# Waveshape_LFO_v1_Controls_SCH.net
KiCad netlist of a schematic drawn in Altium Designer
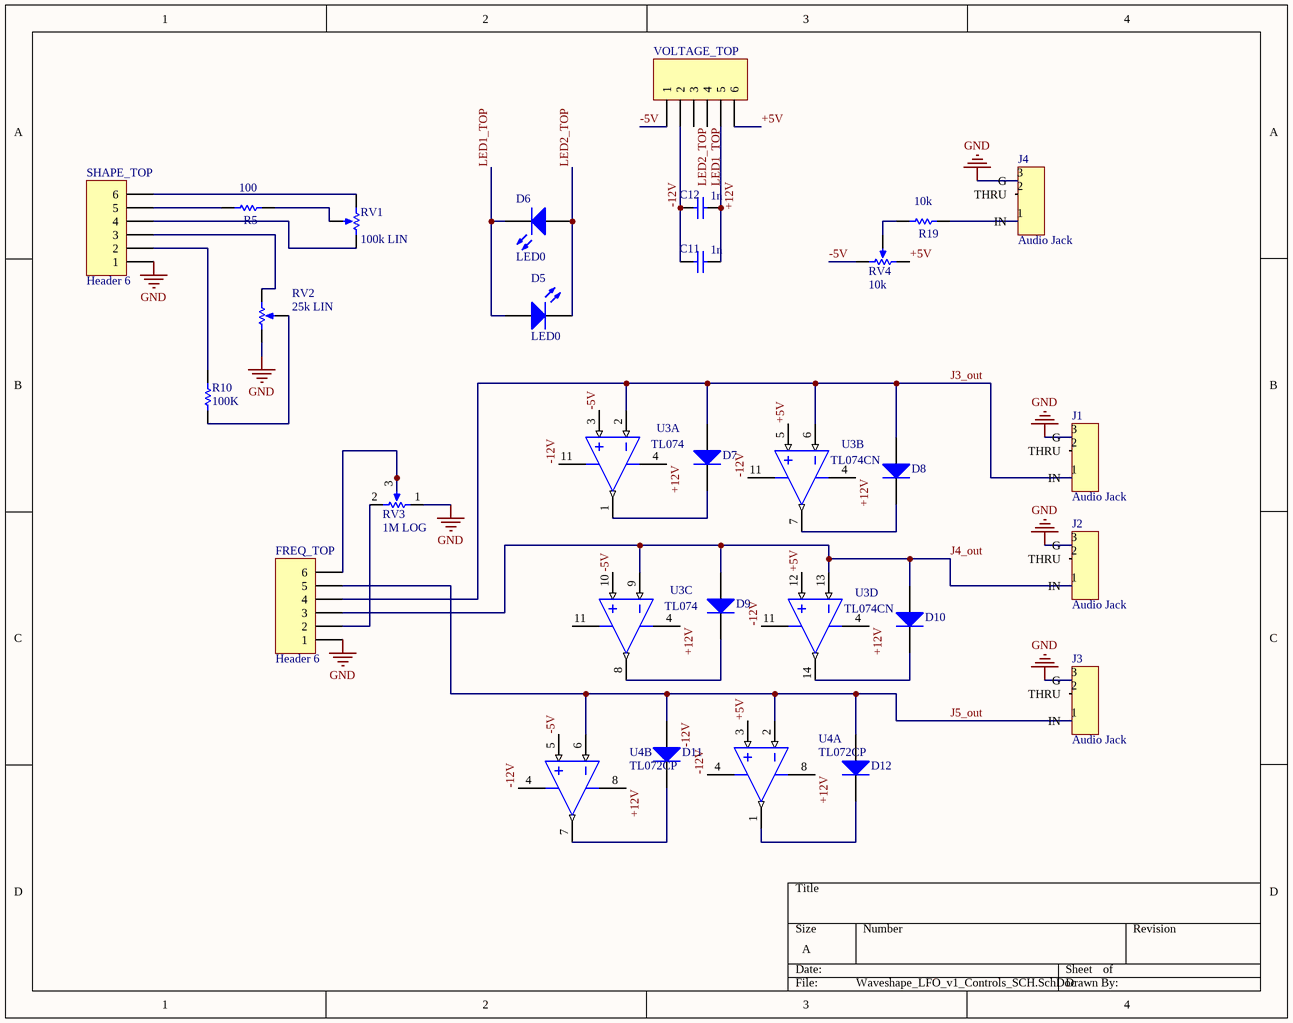
[diagram p0: Waveshape_LFO_v1_Controls_SCH.SchDoc]

(export (version "E")
  (design (tool "Eeschema 10.0.6"))
  (components
    (comp (ref "C11")
      (value "1n")
      (footprint "RAD-0.3")
      (description "Capacitor")
      (fields (field (name "Comment") "Cap") (field (name "PUBLISHER") "Altium Limited"))
      (libsource (lib "Miscellaneous Devices") (part "Cap"))
    )
    (comp (ref "C12")
      (value "1n")
      (footprint "RAD-0.3")
      (description "Capacitor")
      (fields (field (name "Comment") "Cap") (field (name "PUBLISHER") "Altium Limited"))
      (libsource (lib "Miscellaneous Devices") (part "Cap"))
    )
    (comp (ref "D5")
      (value "LED0")
      (footprint "LED-1")
      (description "Typical INFRARED GaAs LED")
      (fields (field (name "PUBLISHER") "Altium Limited"))
      (libsource (lib "Miscellaneous Devices") (part "LED0"))
    )
    (comp (ref "D6")
      (value "LED0")
      (footprint "LED-1")
      (description "Typical INFRARED GaAs LED")
      (fields (field (name "PUBLISHER") "Altium Limited"))
      (libsource (lib "Miscellaneous Devices") (part "LED0"))
    )
    (comp (ref "D7")
      (value "Diode 1N4148")
      (footprint "DO-35")
      (description "High Conductance Fast Diode")
      (fields (field (name "PUBLISHER") "Altium Limited"))
      (libsource (lib "Miscellaneous Devices") (part "Diode 1N4148"))
    )
    (comp (ref "D8")
      (value "Diode 1N4148")
      (footprint "DO-35")
      (description "High Conductance Fast Diode")
      (fields (field (name "PUBLISHER") "Altium Limited"))
      (libsource (lib "Miscellaneous Devices") (part "Diode 1N4148"))
    )
    (comp (ref "D9")
      (value "Diode 1N4148")
      (footprint "DO-35")
      (description "High Conductance Fast Diode")
      (fields (field (name "PUBLISHER") "Altium Limited"))
      (libsource (lib "Miscellaneous Devices") (part "Diode 1N4148"))
    )
    (comp (ref "D10")
      (value "Diode 1N4148")
      (footprint "DO-35")
      (description "High Conductance Fast Diode")
      (fields (field (name "PUBLISHER") "Altium Limited"))
      (libsource (lib "Miscellaneous Devices") (part "Diode 1N4148"))
    )
    (comp (ref "D11")
      (value "Diode 1N4148")
      (footprint "DO-35")
      (description "High Conductance Fast Diode")
      (fields (field (name "PUBLISHER") "Altium Limited"))
      (libsource (lib "Miscellaneous Devices") (part "Diode 1N4148"))
    )
    (comp (ref "D12")
      (value "Diode 1N4148")
      (footprint "DO-35")
      (description "High Conductance Fast Diode")
      (fields (field (name "PUBLISHER") "Altium Limited"))
      (libsource (lib "Miscellaneous Devices") (part "Diode 1N4148"))
    )
    (comp (ref "FREQ_TOP")
      (value "Header 6")
      (footprint "HDR1X6")
      (description "Header, 6-Pin")
      (fields (field (name "PUBLISHER") "Altium Limited"))
      (libsource (lib "Miscellaneous Connectors") (part "Header 6"))
    )
    (comp (ref "J1")
      (value "Audio Jack")
      (footprint "Audio Jack")
      (libsource (lib "DIYSynth") (part "Audio Jack"))
    )
    (comp (ref "J2")
      (value "Audio Jack")
      (footprint "Audio Jack")
      (libsource (lib "DIYSynth") (part "Audio Jack"))
    )
    (comp (ref "J3")
      (value "Audio Jack")
      (footprint "Audio Jack")
      (libsource (lib "DIYSynth") (part "Audio Jack"))
    )
    (comp (ref "J4")
      (value "Audio Jack")
      (footprint "Audio Jack")
      (libsource (lib "DIYSynth") (part "Audio Jack"))
    )
    (comp (ref "R5")
      (value "100")
      (footprint "AXIAL-0.3")
      (description "Resistor")
      (fields (field (name "PUBLISHER") "Altium Limited"))
      (libsource (lib "Miscellaneous Devices") (part "Res1"))
    )
    (comp (ref "R10")
      (value "100K")
      (footprint "AXIAL-0.3")
      (description "Resistor")
      (fields (field (name "PUBLISHER") "Altium Limited"))
      (libsource (lib "Miscellaneous Devices") (part "Res1"))
    )
    (comp (ref "R19")
      (value "10k")
      (footprint "AXIAL-0.3")
      (description "Resistor")
      (fields (field (name "PUBLISHER") "Altium Limited"))
      (libsource (lib "Miscellaneous Devices") (part "Res1"))
    )
    (comp (ref "RV1")
      (value "100k LIN")
      (footprint "VR5")
      (description "Potentiometer")
      (fields (field (name "Comment") "RPot") (field (name "PUBLISHER") "Altium Limited"))
      (libsource (lib "Miscellaneous Devices") (part "RPot"))
    )
    (comp (ref "RV2")
      (value "25k LIN")
      (footprint "VR5")
      (description "Potentiometer")
      (fields (field (name "Comment") "j") (field (name "PUBLISHER") "Altium Limited"))
      (libsource (lib "Miscellaneous Devices") (part "RPot"))
    )
    (comp (ref "RV3")
      (value "1M LOG")
      (footprint "VR5")
      (description "Potentiometer")
      (fields (field (name "Comment") "RPot") (field (name "PUBLISHER") "Altium Limited"))
      (libsource (lib "") (part "RPot_1"))
    )
    (comp (ref "RV4")
      (value "10k")
      (footprint "VR5")
      (description "Potentiometer")
      (fields (field (name "Comment") "RPot") (field (name "PUBLISHER") "Altium Limited"))
      (libsource (lib "Miscellaneous Devices") (part "RPot"))
    )
    (comp (ref "SHAPE_TOP")
      (value "Header 6")
      (footprint "HDR1X6")
      (description "Header, 6-Pin")
      (fields (field (name "PUBLISHER") "Altium Limited"))
      (libsource (lib "Miscellaneous Connectors") (part "Header 6"))
    )
    (comp (ref "U3")
      (value "TL074")
      (footprint "N0014A")
      (fields (field (name "MANUFACTURER") "Texas Instruments") (field (name "PARTNUMBER") "TL074CN"))
      (libsource (lib "Altium Content Vault") (part "TI-TLXX4X_MC3403-X14"))
    )
    (comp (ref "U4")
      (value "TL072CP")
      (footprint "P0008A")
      (fields (field (name "MANUFACTURER") "Texas Instruments"))
      (libsource (lib "Altium Content Vault") (part "TI-AMP-D6-2-8_D"))
    )
    (comp (ref "VOLTAGE_TOP")
      (value "Header 6")
      (footprint "HDR1X6")
      (description "Header, 6-Pin")
      (fields (field (name "PUBLISHER") "Altium Limited"))
      (libsource (lib "") (part "Header 6_1"))
    )
  )
  (nets
    (net (code "1") (name "/+5V") (class "Default")
      (node (ref "RV4") (pin "1") (pinfunction "TOP_1") (pintype "passive"))
      (node (ref "U3") (pin "12") (pinfunction "IN4+_12") (pintype "input"))
      (node (ref "U3") (pin "5") (pinfunction "IN2+_5") (pintype "input"))
      (node (ref "U4") (pin "3") (pinfunction "IN1+_3") (pintype "input"))
      (node (ref "VOLTAGE_TOP") (pin "6") (pinfunction "6_6") (pintype "passive"))
    )
    (net (code "2") (name "/+12V") (class "Default")
      (node (ref "C11") (pin "2") (pinfunction "2_2") (pintype "passive"))
      (node (ref "C12") (pin "2") (pinfunction "2_2") (pintype "passive"))
      (node (ref "U3") (pin "4") (pinfunction "VCC+_4") (pintype "power_in"))
      (node (ref "U4") (pin "8") (pinfunction "VCC+_8") (pintype "power_in"))
      (node (ref "VOLTAGE_TOP") (pin "5") (pinfunction "5_5") (pintype "passive"))
    )
    (net (code "3") (name "/-5V") (class "Default")
      (node (ref "RV4") (pin "2") (pinfunction "BOT_2") (pintype "passive"))
      (node (ref "U3") (pin "10") (pinfunction "IN3+_10") (pintype "input"))
      (node (ref "U3") (pin "3") (pinfunction "IN1+_3") (pintype "input"))
      (node (ref "U4") (pin "5") (pinfunction "IN2+_5") (pintype "input"))
      (node (ref "VOLTAGE_TOP") (pin "1") (pinfunction "1_1") (pintype "passive"))
    )
    (net (code "4") (name "/-12V") (class "Default")
      (node (ref "C11") (pin "1") (pinfunction "1_1") (pintype "passive"))
      (node (ref "C12") (pin "1") (pinfunction "1_1") (pintype "passive"))
      (node (ref "U3") (pin "11") (pinfunction "VCC-_11") (pintype "power_in"))
      (node (ref "U4") (pin "4") (pinfunction "VCC-_4") (pintype "power_in"))
      (node (ref "VOLTAGE_TOP") (pin "2") (pinfunction "2_2") (pintype "passive"))
    )
    (net (code "5") (name "/J3_out") (class "Default")
      (node (ref "D7") (pin "1") (pinfunction "A_1") (pintype "passive"))
      (node (ref "D8") (pin "1") (pinfunction "A_1") (pintype "passive"))
      (node (ref "FREQ_TOP") (pin "4") (pinfunction "4_4") (pintype "passive"))
      (node (ref "J1") (pin "1") (pinfunction "IN_1") (pintype "passive"))
      (node (ref "U3") (pin "2") (pinfunction "IN1-_2") (pintype "input"))
      (node (ref "U3") (pin "6") (pinfunction "IN2-_6") (pintype "input"))
    )
    (net (code "6") (name "/J4_out") (class "Default")
      (node (ref "D10") (pin "1") (pinfunction "A_1") (pintype "passive"))
      (node (ref "D9") (pin "1") (pinfunction "A_1") (pintype "passive"))
      (node (ref "FREQ_TOP") (pin "3") (pinfunction "3_3") (pintype "passive"))
      (node (ref "J2") (pin "1") (pinfunction "IN_1") (pintype "passive"))
      (node (ref "U3") (pin "13") (pinfunction "IN4-_13") (pintype "input"))
      (node (ref "U3") (pin "9") (pinfunction "IN3-_9") (pintype "input"))
    )
    (net (code "7") (name "/J5_out") (class "Default")
      (node (ref "D11") (pin "1") (pinfunction "A_1") (pintype "passive"))
      (node (ref "D12") (pin "1") (pinfunction "A_1") (pintype "passive"))
      (node (ref "FREQ_TOP") (pin "5") (pinfunction "5_5") (pintype "passive"))
      (node (ref "J3") (pin "1") (pinfunction "IN_1") (pintype "passive"))
      (node (ref "U4") (pin "2") (pinfunction "IN1-_2") (pintype "input"))
      (node (ref "U4") (pin "6") (pinfunction "IN2-_6") (pintype "input"))
    )
    (net (code "8") (name "/LED1_TOP") (class "Default")
      (node (ref "D5") (pin "1") (pinfunction "A_1") (pintype "passive"))
      (node (ref "D6") (pin "2") (pinfunction "K_2") (pintype "passive"))
      (node (ref "VOLTAGE_TOP") (pin "4") (pinfunction "4_4") (pintype "passive"))
    )
    (net (code "9") (name "/LED2_TOP") (class "Default")
      (node (ref "D5") (pin "2") (pinfunction "K_2") (pintype "passive"))
      (node (ref "D6") (pin "1") (pinfunction "A_1") (pintype "passive"))
      (node (ref "VOLTAGE_TOP") (pin "3") (pinfunction "3_3") (pintype "passive"))
    )
    (net (code "10") (name "GND") (class "Default")
      (node (ref "FREQ_TOP") (pin "1") (pinfunction "1_1") (pintype "passive"))
      (node (ref "J1") (pin "3") (pinfunction "G_3") (pintype "passive"))
      (node (ref "J2") (pin "3") (pinfunction "G_3") (pintype "passive"))
      (node (ref "J3") (pin "3") (pinfunction "G_3") (pintype "passive"))
      (node (ref "J4") (pin "3") (pinfunction "G_3") (pintype "passive"))
      (node (ref "RV2") (pin "1") (pinfunction "TOP_1") (pintype "passive"))
      (node (ref "RV3") (pin "1") (pinfunction "TOP_1") (pintype "passive"))
      (node (ref "SHAPE_TOP") (pin "1") (pinfunction "1_1") (pintype "passive"))
    )
    (net (code "11") (name "Net-(D7-K)") (class "Default")
      (node (ref "D7") (pin "2") (pinfunction "K_2") (pintype "passive"))
      (node (ref "U3") (pin "1") (pinfunction "OUT1_1") (pintype "output"))
    )
    (net (code "12") (name "Net-(D8-K)") (class "Default")
      (node (ref "D8") (pin "2") (pinfunction "K_2") (pintype "passive"))
      (node (ref "U3") (pin "7") (pinfunction "OUT2_7") (pintype "output"))
    )
    (net (code "13") (name "Net-(D9-K)") (class "Default")
      (node (ref "D9") (pin "2") (pinfunction "K_2") (pintype "passive"))
      (node (ref "U3") (pin "8") (pinfunction "OUT3_8") (pintype "output"))
    )
    (net (code "14") (name "Net-(D10-K)") (class "Default")
      (node (ref "D10") (pin "2") (pinfunction "K_2") (pintype "passive"))
      (node (ref "U3") (pin "14") (pinfunction "OUT4_14") (pintype "output"))
    )
    (net (code "15") (name "Net-(D11-K)") (class "Default")
      (node (ref "D11") (pin "2") (pinfunction "K_2") (pintype "passive"))
      (node (ref "U4") (pin "7") (pinfunction "OUT2_7") (pintype "output"))
    )
    (net (code "16") (name "Net-(D12-K)") (class "Default")
      (node (ref "D12") (pin "2") (pinfunction "K_2") (pintype "passive"))
      (node (ref "U4") (pin "1") (pinfunction "OUT1_1") (pintype "output"))
    )
    (net (code "17") (name "Net-(J4-IN)") (class "Default")
      (node (ref "J4") (pin "1") (pinfunction "IN_1") (pintype "passive"))
      (node (ref "R19") (pin "2") (pinfunction "2_2") (pintype "passive"))
    )
    (net (code "18") (name "Net-(R5-Pad1)") (class "Default")
      (node (ref "R5") (pin "1") (pinfunction "1_1") (pintype "passive"))
      (node (ref "SHAPE_TOP") (pin "5") (pinfunction "5_5") (pintype "passive"))
    )
    (net (code "19") (name "Net-(R10-Pad2)") (class "Default")
      (node (ref "R10") (pin "2") (pinfunction "2_2") (pintype "passive"))
      (node (ref "SHAPE_TOP") (pin "2") (pinfunction "2_2") (pintype "passive"))
    )
    (net (code "20") (name "Net-(RV1-BOT)") (class "Default")
      (node (ref "RV1") (pin "2") (pinfunction "BOT_2") (pintype "passive"))
      (node (ref "SHAPE_TOP") (pin "4") (pinfunction "4_4") (pintype "passive"))
    )
    (net (code "21") (name "Net-(RV1-TAP)") (class "Default")
      (node (ref "R5") (pin "2") (pinfunction "2_2") (pintype "passive"))
      (node (ref "RV1") (pin "3") (pinfunction "TAP_3") (pintype "passive"))
    )
    (net (code "22") (name "Net-(RV1-TOP)") (class "Default")
      (node (ref "RV1") (pin "1") (pinfunction "TOP_1") (pintype "passive"))
      (node (ref "SHAPE_TOP") (pin "6") (pinfunction "6_6") (pintype "passive"))
    )
    (net (code "23") (name "Net-(RV2-BOT)") (class "Default")
      (node (ref "RV2") (pin "2") (pinfunction "BOT_2") (pintype "passive"))
      (node (ref "SHAPE_TOP") (pin "3") (pinfunction "3_3") (pintype "passive"))
    )
    (net (code "24") (name "Net-(RV2-TAP)") (class "Default")
      (node (ref "R10") (pin "1") (pinfunction "1_1") (pintype "passive"))
      (node (ref "RV2") (pin "3") (pinfunction "TAP_3") (pintype "passive"))
    )
    (net (code "25") (name "Net-(RV3-BOT)") (class "Default")
      (node (ref "FREQ_TOP") (pin "2") (pinfunction "2_2") (pintype "passive"))
      (node (ref "RV3") (pin "2") (pinfunction "BOT_2") (pintype "passive"))
    )
    (net (code "26") (name "Net-(RV3-TAP)") (class "Default")
      (node (ref "FREQ_TOP") (pin "6") (pinfunction "6_6") (pintype "passive"))
      (node (ref "RV3") (pin "3") (pinfunction "TAP_3") (pintype "passive"))
    )
    (net (code "27") (name "Net-(RV4-TAP)") (class "Default")
      (node (ref "R19") (pin "1") (pinfunction "1_1") (pintype "passive"))
      (node (ref "RV4") (pin "3") (pinfunction "TAP_3") (pintype "passive"))
    )
    (net (code "28") (name "unconnected-(J1-THRU-Pad2)") (class "Default")
      (node (ref "J1") (pin "2") (pinfunction "THRU_2") (pintype "passive"))
    )
    (net (code "29") (name "unconnected-(J2-THRU-Pad2)") (class "Default")
      (node (ref "J2") (pin "2") (pinfunction "THRU_2") (pintype "passive"))
    )
    (net (code "30") (name "unconnected-(J3-THRU-Pad2)") (class "Default")
      (node (ref "J3") (pin "2") (pinfunction "THRU_2") (pintype "passive"))
    )
    (net (code "31") (name "unconnected-(J4-THRU-Pad2)") (class "Default")
      (node (ref "J4") (pin "2") (pinfunction "THRU_2") (pintype "passive"))
    )
    (net (code "32") (name "unconnected-(U3C-VCC--Pad11)") (class "Default")
      (node (ref "U3") (pin "11") (pinfunction "VCC-_11") (pintype "power_in"))
    )
  )
)
